# Micro.net
KiCad netlist of a schematic drawn in Altium Designer
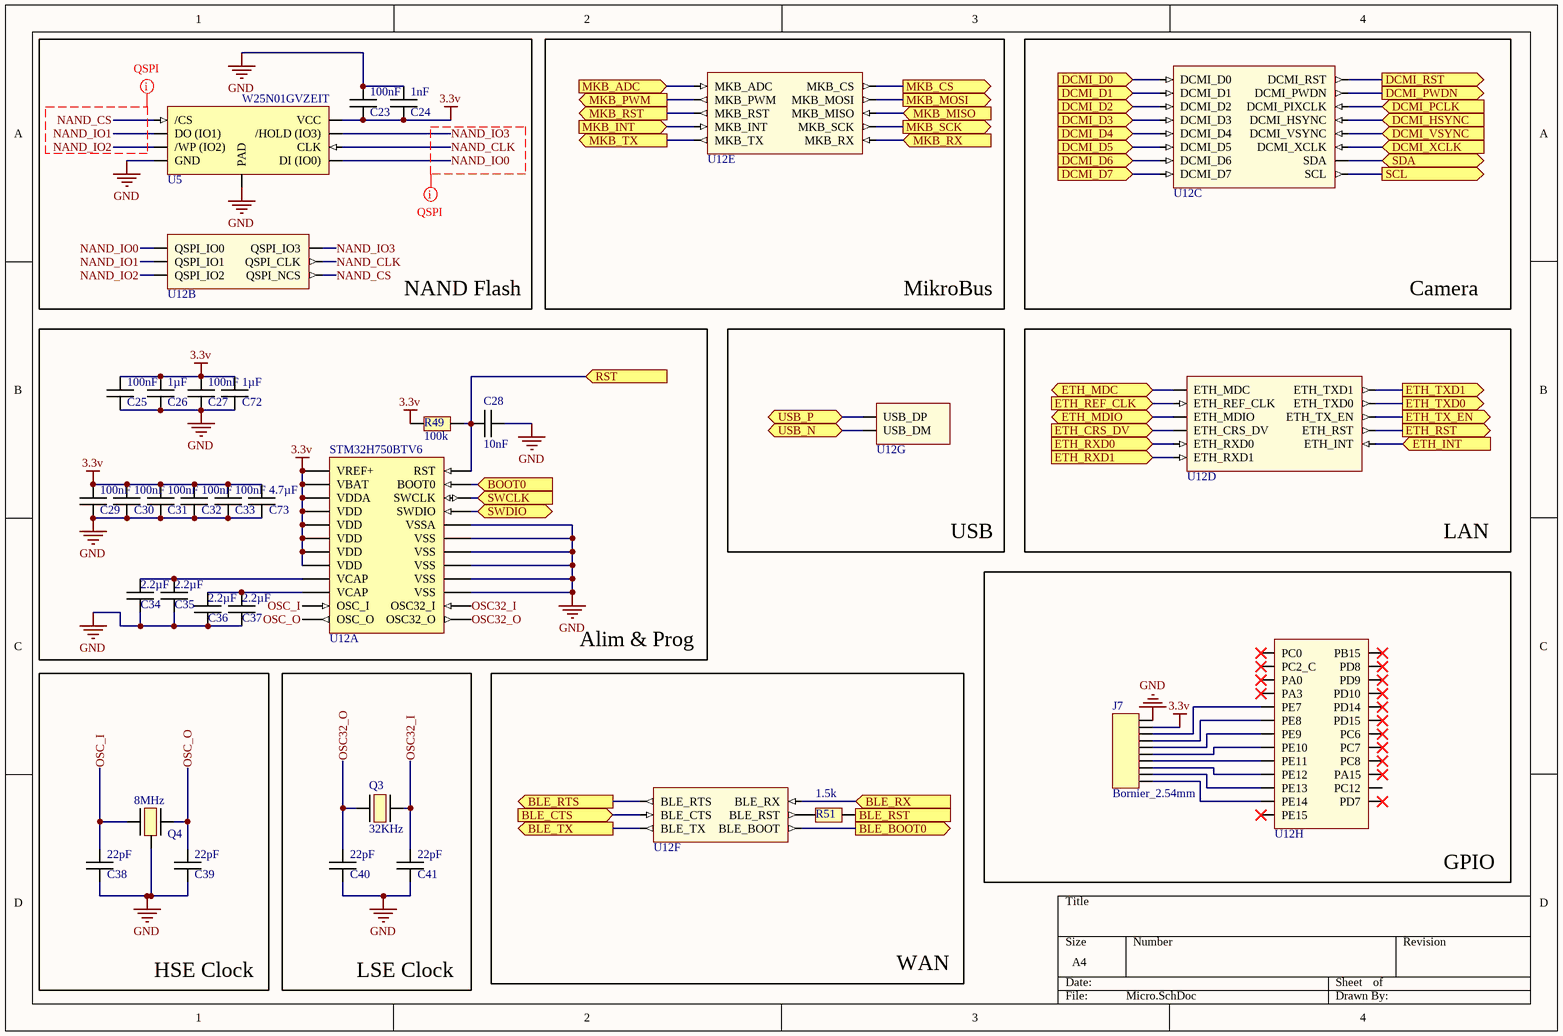
[diagram p0: Micro.SchDoc]

(export (version "E")
  (design (tool "Eeschema 10.0.6"))
  (components
    (comp (ref "C23")
      (value "100nF")
      (footprint "0603")
      (libsource (lib "Carte_design_SCHLib") (part "Capa"))
    )
    (comp (ref "C24") (value "1nF") (footprint "0603") (libsource (lib "Carte_design_SCHLib") (part "Capa")))
    (comp (ref "C25")
      (value "100nF")
      (footprint "0603")
      (libsource (lib "Carte_design_SCHLib") (part "Capa"))
    )
    (comp (ref "C26") (value "1µF") (footprint "0603") (libsource (lib "Carte_design_SCHLib") (part "Capa")))
    (comp (ref "C27")
      (value "100nF")
      (footprint "0603")
      (libsource (lib "Carte_design_SCHLib") (part "Capa"))
    )
    (comp (ref "C28") (value "10nF") (footprint "0603") (libsource (lib "Carte_design_SCHLib") (part "Capa")))
    (comp (ref "C29")
      (value "100nF")
      (footprint "0603")
      (libsource (lib "Carte_design_SCHLib") (part "Capa"))
    )
    (comp (ref "C30")
      (value "100nF")
      (footprint "0603")
      (libsource (lib "Carte_design_SCHLib") (part "Capa"))
    )
    (comp (ref "C31")
      (value "100nF")
      (footprint "0603")
      (libsource (lib "Carte_design_SCHLib") (part "Capa"))
    )
    (comp (ref "C32")
      (value "100nF")
      (footprint "0603")
      (libsource (lib "Carte_design_SCHLib") (part "Capa"))
    )
    (comp (ref "C33")
      (value "100nF")
      (footprint "0603")
      (libsource (lib "Carte_design_SCHLib") (part "Capa"))
    )
    (comp (ref "C34")
      (value "2.2µF")
      (footprint "0603")
      (libsource (lib "Carte_design_SCHLib") (part "Capa"))
    )
    (comp (ref "C35")
      (value "2.2µF")
      (footprint "0603")
      (libsource (lib "Carte_design_SCHLib") (part "Capa"))
    )
    (comp (ref "C36")
      (value "2.2µF")
      (footprint "0603")
      (libsource (lib "Carte_design_SCHLib") (part "Capa"))
    )
    (comp (ref "C37")
      (value "2.2µF")
      (footprint "0603")
      (libsource (lib "Carte_design_SCHLib") (part "Capa"))
    )
    (comp (ref "C38") (value "22pF") (footprint "0603") (libsource (lib "Carte_design_SCHLib") (part "Capa")))
    (comp (ref "C39") (value "22pF") (footprint "0603") (libsource (lib "Carte_design_SCHLib") (part "Capa")))
    (comp (ref "C40") (value "22pF") (footprint "0603") (libsource (lib "Carte_design_SCHLib") (part "Capa")))
    (comp (ref "C41") (value "22pF") (footprint "0603") (libsource (lib "Carte_design_SCHLib") (part "Capa")))
    (comp (ref "C72") (value "1µF") (footprint "0603") (libsource (lib "Carte_design_SCHLib") (part "Capa")))
    (comp (ref "C73")
      (value "4.7µF")
      (footprint "0603")
      (libsource (lib "Carte_design_SCHLib") (part "Capa"))
    )
    (comp (ref "J7")
      (value "Bornier_2.54mm")
      (footprint "GPIO_header")
      (libsource (lib "Carte_design_SCHLib") (part "GPIO_bornier"))
    )
    (comp (ref "Q3")
      (value "32KHz")
      (footprint "BLE_Quartz_Sxtal")
      (libsource (lib "Carte_design_SCHLib") (part "BLE_quartz_Sxtal"))
    )
    (comp (ref "Q4")
      (value "8MHz")
      (footprint "Quartz_Micro_HF")
      (libsource (lib "Carte_design_SCHLib") (part "Quartz_micro_HF"))
    )
    (comp (ref "R49")
      (value "100k")
      (footprint "0603")
      (libsource (lib "Carte_design_SCHLib") (part "Resistance"))
    )
    (comp (ref "R51")
      (value "1.5k")
      (footprint "0603")
      (libsource (lib "Carte_design_SCHLib") (part "Resistance"))
    )
    (comp (ref "U5")
      (value "W25N01GVZEIT")
      (footprint "SON127P800X80_HS-9M")
      (libsource (lib "Carte_design_SCHLib") (part "W25N01GVZEIT"))
    )
    (comp (ref "U12")
      (value "STM32H750BTV6")
      (footprint "LQFP100_14x14_0.5pitch")
      (libsource (lib "Carte_design_SCHLib") (part "STM32H750BTV6"))
    )
  )
  (nets
    (net (code "1") (name "/BLE_BOOT0") (class "Default")
      (node (ref "U12") (pin "81") (pinfunction "BLE_BOOT_81") (pintype "output"))
    )
    (net (code "2") (name "/BLE_CTS") (class "Default")
      (node (ref "U12") (pin "58") (pinfunction "BLE_CTS_58") (pintype "input"))
    )
    (net (code "3") (name "/BLE_RST") (class "Default")
      (node (ref "R51") (pin "1") (pinfunction "26_1") (pintype "passive"))
    )
    (net (code "4") (name "/BLE_RTS") (class "Default")
      (node (ref "U12") (pin "53") (pinfunction "BLE_RTS_53") (pintype "output"))
    )
    (net (code "5") (name "/BLE_RX") (class "Default")
      (node (ref "U12") (pin "79") (pinfunction "BLE_RX_79") (pintype "input"))
    )
    (net (code "6") (name "/BLE_TX") (class "Default")
      (node (ref "U12") (pin "78") (pinfunction "BLE_TX_78") (pintype "output"))
    )
    (net (code "7") (name "/BOOT0") (class "Default")
      (node (ref "U12") (pin "94") (pinfunction "BOOT0_94") (pintype "input"))
    )
    (net (code "8") (name "/DCMI_D0") (class "Default")
      (node (ref "U12") (pin "68") (pinfunction "DCMI_D0_68") (pintype "input"))
    )
    (net (code "9") (name "/DCMI_D1") (class "Default")
      (node (ref "U12") (pin "69") (pinfunction "DCMI_D1_69") (pintype "input"))
    )
    (net (code "10") (name "/DCMI_D2") (class "Default")
      (node (ref "U12") (pin "97") (pinfunction "DCMI_D2_97") (pintype "input"))
    )
    (net (code "11") (name "/DCMI_D3") (class "Default")
      (node (ref "U12") (pin "98") (pinfunction "DCMI_D3_98") (pintype "input"))
    )
    (net (code "12") (name "/DCMI_D4") (class "Default")
      (node (ref "U12") (pin "3") (pinfunction "DCMI_D4_3") (pintype "input"))
    )
    (net (code "13") (name "/DCMI_D5") (class "Default")
      (node (ref "U12") (pin "92") (pinfunction "DCMI_D5_92") (pintype "input"))
    )
    (net (code "14") (name "/DCMI_D6") (class "Default")
      (node (ref "U12") (pin "4") (pinfunction "DCMI_D6_4") (pintype "input"))
    )
    (net (code "15") (name "/DCMI_D7") (class "Default")
      (node (ref "U12") (pin "5") (pinfunction "DCMI_D7_5") (pintype "input"))
    )
    (net (code "16") (name "/DCMI_HSYNC") (class "Default")
      (node (ref "U12") (pin "28") (pinfunction "DCMI_HSYNC_28") (pintype "input"))
    )
    (net (code "17") (name "/DCMI_PCLK") (class "Default")
      (node (ref "U12") (pin "30") (pinfunction "DCMI_PIXCLK_30") (pintype "input"))
    )
    (net (code "18") (name "/DCMI_PWDN") (class "Default")
      (node (ref "U12") (pin "7") (pinfunction "DCMI_PWDN_7") (pintype "output"))
    )
    (net (code "19") (name "/DCMI_RST") (class "Default")
      (node (ref "U12") (pin "2") (pinfunction "DCMI_RST_2") (pintype "output"))
    )
    (net (code "20") (name "/DCMI_VSYNC") (class "Default")
      (node (ref "U12") (pin "93") (pinfunction "DCMI_VSYNC_93") (pintype "input"))
    )
    (net (code "21") (name "/DCMI_XCLK") (class "Default")
      (node (ref "U12") (pin "29") (pinfunction "DCMI_XCLK_29") (pintype "input"))
    )
    (net (code "22") (name "/ETH_CRS_DV") (class "Default")
      (node (ref "U12") (pin "31") (pinfunction "ETH_CRS_DV_31") (pintype "bidirectional"))
    )
    (net (code "23") (name "/ETH_INT") (class "Default")
      (node (ref "U12") (pin "34") (pinfunction "ETH_INT_34") (pintype "input"))
    )
    (net (code "24") (name "/ETH_MDC") (class "Default")
      (node (ref "U12") (pin "16") (pinfunction "ETH_MDC_16") (pintype "bidirectional"))
    )
    (net (code "25") (name "/ETH_MDIO") (class "Default")
      (node (ref "U12") (pin "24") (pinfunction "ETH_MDIO_24") (pintype "bidirectional"))
    )
    (net (code "26") (name "/ETH_REF_CLK") (class "Default")
      (node (ref "U12") (pin "23") (pinfunction "ETH_REF_CLK_23") (pintype "input"))
    )
    (net (code "27") (name "/ETH_RST") (class "Default")
      (node (ref "U12") (pin "35") (pinfunction "ETH_RST_35") (pintype "output"))
    )
    (net (code "28") (name "/ETH_RXD0") (class "Default")
      (node (ref "U12") (pin "32") (pinfunction "ETH_RXD0_32") (pintype "input"))
    )
    (net (code "29") (name "/ETH_RXD1") (class "Default")
      (node (ref "U12") (pin "33") (pinfunction "ETH_RXD1_33") (pintype "input"))
    )
    (net (code "30") (name "/ETH_TXD0") (class "Default")
      (node (ref "U12") (pin "51") (pinfunction "ETH_TXD0_51") (pintype "output"))
    )
    (net (code "31") (name "/ETH_TXD1") (class "Default")
      (node (ref "U12") (pin "52") (pinfunction "ETH_TXD1_52") (pintype "output"))
    )
    (net (code "32") (name "/ETH_TX_EN") (class "Default")
      (node (ref "U12") (pin "47") (pinfunction "ETH_TX_EN_47") (pintype "output"))
    )
    (net (code "33") (name "/MKB_ADC") (class "Default")
      (node (ref "U12") (pin "18") (pinfunction "MKB_ADC_18") (pintype "input"))
    )
    (net (code "34") (name "/MKB_CS") (class "Default")
      (node (ref "U12") (pin "85") (pinfunction "MKB_CS_85") (pintype "output"))
    )
    (net (code "35") (name "/MKB_INT") (class "Default")
      (node (ref "U12") (pin "84") (pinfunction "MKB_INT_84") (pintype "input"))
    )
    (net (code "36") (name "/MKB_MISO") (class "Default")
      (node (ref "U12") (pin "90") (pinfunction "MKB_MISO_90") (pintype "input"))
    )
    (net (code "37") (name "/MKB_MOSI") (class "Default")
      (node (ref "U12") (pin "91") (pinfunction "MKB_MOSI_91") (pintype "output"))
    )
    (net (code "38") (name "/MKB_PWM") (class "Default")
      (node (ref "U12") (pin "67") (pinfunction "MKB_PWM_67") (pintype "output"))
    )
    (net (code "39") (name "/MKB_RST") (class "Default")
      (node (ref "U12") (pin "83") (pinfunction "MKB_RST_83") (pintype "output"))
    )
    (net (code "40") (name "/MKB_RX") (class "Default")
      (node (ref "U12") (pin "87") (pinfunction "MKB_RX_87") (pintype "input"))
    )
    (net (code "41") (name "/MKB_SCK") (class "Default")
      (node (ref "U12") (pin "89") (pinfunction "MKB_SCK_89") (pintype "output"))
    )
    (net (code "42") (name "/MKB_TX") (class "Default")
      (node (ref "U12") (pin "86") (pinfunction "MKB_TX_86") (pintype "output"))
    )
    (net (code "43") (name "/NAND_CLK") (class "Default")
      (node (ref "U12") (pin "36") (pinfunction "QSPI_CLK_36") (pintype "output"))
      (node (ref "U5") (pin "6") (pinfunction "CLK_6") (pintype "input"))
    )
    (net (code "44") (name "/NAND_CS") (class "Default")
      (node (ref "U12") (pin "46") (pinfunction "QSPI_NCS_46") (pintype "output"))
      (node (ref "U5") (pin "1") (pinfunction "/CS_1") (pintype "input"))
    )
    (net (code "45") (name "/NAND_IO0") (class "Default")
      (node (ref "U12") (pin "66") (pinfunction "QSPI_IO0_66") (pintype "bidirectional"))
      (node (ref "U5") (pin "5") (pinfunction "DI_(IO0)_5") (pintype "bidirectional"))
    )
    (net (code "46") (name "/NAND_IO1") (class "Default")
      (node (ref "U12") (pin "59") (pinfunction "QSPI_IO1_59") (pintype "bidirectional"))
      (node (ref "U5") (pin "2") (pinfunction "DO_(IO1)_2") (pintype "bidirectional"))
    )
    (net (code "47") (name "/NAND_IO2") (class "Default")
      (node (ref "U12") (pin "1") (pinfunction "QSPI_IO2_1") (pintype "bidirectional"))
      (node (ref "U5") (pin "3") (pinfunction "/WP_(IO2)_3") (pintype "bidirectional"))
    )
    (net (code "48") (name "/NAND_IO3") (class "Default")
      (node (ref "U12") (pin "60") (pinfunction "QSPI_IO3_60") (pintype "bidirectional"))
      (node (ref "U5") (pin "7") (pinfunction "/HOLD_(IO3)_7") (pintype "bidirectional"))
    )
    (net (code "49") (name "/OSC32_I") (class "Default")
      (node (ref "C41") (pin "2") (pinfunction "28_2") (pintype "passive"))
      (node (ref "Q3") (pin "1") (pinfunction "15_1") (pintype "passive"))
      (node (ref "U12") (pin "8") (pinfunction "OSC32_I_8") (pintype "input"))
    )
    (net (code "50") (name "/OSC32_O") (class "Default")
      (node (ref "C40") (pin "2") (pinfunction "28_2") (pintype "passive"))
      (node (ref "Q3") (pin "2") (pinfunction "16_2") (pintype "passive"))
      (node (ref "U12") (pin "9") (pinfunction "OSC32_O_9") (pintype "output"))
    )
    (net (code "51") (name "/OSC_I") (class "Default")
      (node (ref "C38") (pin "2") (pinfunction "28_2") (pintype "passive"))
      (node (ref "Q4") (pin "1") (pinfunction "15_1") (pintype "passive"))
      (node (ref "U12") (pin "12") (pinfunction "OSC_I_12") (pintype "input"))
    )
    (net (code "52") (name "/OSC_O") (class "Default")
      (node (ref "C39") (pin "2") (pinfunction "28_2") (pintype "passive"))
      (node (ref "Q4") (pin "2") (pinfunction "16_2") (pintype "passive"))
      (node (ref "U12") (pin "13") (pinfunction "OSC_O_13") (pintype "output"))
    )
    (net (code "53") (name "/RST") (class "Default")
      (node (ref "C28") (pin "2") (pinfunction "28_2") (pintype "passive"))
      (node (ref "R49") (pin "1") (pinfunction "26_1") (pintype "passive"))
      (node (ref "U12") (pin "14") (pinfunction "RST_14") (pintype "input"))
    )
    (net (code "54") (name "/SCL") (class "Default")
      (node (ref "U12") (pin "95") (pinfunction "SCL_95") (pintype "output"))
    )
    (net (code "55") (name "/SDA") (class "Default")
      (node (ref "U12") (pin "96") (pinfunction "SDA_96") (pintype "bidirectional"))
    )
    (net (code "56") (name "/SWCLK") (class "Default")
      (node (ref "U12") (pin "76") (pinfunction "SWCLK_76") (pintype "bidirectional"))
    )
    (net (code "57") (name "/SWDIO") (class "Default")
      (node (ref "U12") (pin "72") (pinfunction "SWDIO_72") (pintype "input"))
    )
    (net (code "58") (name "/USB_N") (class "Default")
      (node (ref "U12") (pin "70") (pinfunction "USB_DM_70") (pintype "bidirectional"))
    )
    (net (code "59") (name "/USB_P") (class "Default")
      (node (ref "U12") (pin "71") (pinfunction "USB_DP_71") (pintype "bidirectional"))
    )
    (net (code "60") (name "3.3v") (class "Default")
      (node (ref "C23") (pin "1") (pinfunction "29_1") (pintype "passive"))
      (node (ref "C24") (pin "1") (pinfunction "29_1") (pintype "passive"))
      (node (ref "C25") (pin "2") (pinfunction "28_2") (pintype "passive"))
      (node (ref "C26") (pin "2") (pinfunction "28_2") (pintype "passive"))
      (node (ref "C27") (pin "2") (pinfunction "28_2") (pintype "passive"))
      (node (ref "C29") (pin "2") (pinfunction "28_2") (pintype "passive"))
      (node (ref "C30") (pin "2") (pinfunction "28_2") (pintype "passive"))
      (node (ref "C31") (pin "2") (pinfunction "28_2") (pintype "passive"))
      (node (ref "C32") (pin "2") (pinfunction "28_2") (pintype "passive"))
      (node (ref "C33") (pin "2") (pinfunction "28_2") (pintype "passive"))
      (node (ref "C72") (pin "2") (pinfunction "28_2") (pintype "passive"))
      (node (ref "C73") (pin "2") (pinfunction "28_2") (pintype "passive"))
      (node (ref "J7") (pin "9") (pintype "passive"))
      (node (ref "R49") (pin "2") (pinfunction "27_2") (pintype "passive"))
      (node (ref "U12") (pin "100") (pinfunction "VDD_100") (pintype "power_in"))
      (node (ref "U12") (pin "11") (pinfunction "VDD_11") (pintype "power_in"))
      (node (ref "U12") (pin "20") (pinfunction "VREF+_20") (pintype "power_in"))
      (node (ref "U12") (pin "21") (pinfunction "VDDA_21") (pintype "power_in"))
      (node (ref "U12") (pin "27") (pinfunction "VDD_27") (pintype "power_in"))
      (node (ref "U12") (pin "50") (pinfunction "VDD_50") (pintype "power_in"))
      (node (ref "U12") (pin "6") (pinfunction "VBAT_6") (pintype "power_in"))
      (node (ref "U12") (pin "75") (pinfunction "VDD_75") (pintype "power_in"))
      (node (ref "U5") (pin "8") (pinfunction "VCC_8") (pintype "power_in"))
    )
    (net (code "61") (name "GND") (class "Default")
      (node (ref "C23") (pin "2") (pinfunction "28_2") (pintype "passive"))
      (node (ref "C24") (pin "2") (pinfunction "28_2") (pintype "passive"))
      (node (ref "C25") (pin "1") (pinfunction "29_1") (pintype "passive"))
      (node (ref "C26") (pin "1") (pinfunction "29_1") (pintype "passive"))
      (node (ref "C27") (pin "1") (pinfunction "29_1") (pintype "passive"))
      (node (ref "C28") (pin "1") (pinfunction "29_1") (pintype "passive"))
      (node (ref "C29") (pin "1") (pinfunction "29_1") (pintype "passive"))
      (node (ref "C30") (pin "1") (pinfunction "29_1") (pintype "passive"))
      (node (ref "C31") (pin "1") (pinfunction "29_1") (pintype "passive"))
      (node (ref "C32") (pin "1") (pinfunction "29_1") (pintype "passive"))
      (node (ref "C33") (pin "1") (pinfunction "29_1") (pintype "passive"))
      (node (ref "C34") (pin "1") (pinfunction "29_1") (pintype "passive"))
      (node (ref "C35") (pin "1") (pinfunction "29_1") (pintype "passive"))
      (node (ref "C36") (pin "1") (pinfunction "29_1") (pintype "passive"))
      (node (ref "C37") (pin "1") (pinfunction "29_1") (pintype "passive"))
      (node (ref "C38") (pin "1") (pinfunction "29_1") (pintype "passive"))
      (node (ref "C39") (pin "1") (pinfunction "29_1") (pintype "passive"))
      (node (ref "C40") (pin "1") (pinfunction "29_1") (pintype "passive"))
      (node (ref "C41") (pin "1") (pinfunction "29_1") (pintype "passive"))
      (node (ref "C72") (pin "1") (pinfunction "29_1") (pintype "passive"))
      (node (ref "C73") (pin "1") (pinfunction "29_1") (pintype "passive"))
      (node (ref "J7") (pin "10") (pintype "passive"))
      (node (ref "Q4") (pin "3") (pinfunction "3_3") (pintype "passive"))
      (node (ref "U12") (pin "10") (pinfunction "VSS_10") (pintype "power_in"))
      (node (ref "U12") (pin "19") (pinfunction "VSSA_19") (pintype "power_in"))
      (node (ref "U12") (pin "26") (pinfunction "VSS_26") (pintype "power_in"))
      (node (ref "U12") (pin "49") (pinfunction "VSS_49") (pintype "power_in"))
      (node (ref "U12") (pin "74") (pinfunction "VSS_74") (pintype "power_in"))
      (node (ref "U12") (pin "99") (pinfunction "VSS_99") (pintype "power_in"))
      (node (ref "U5") (pin "4") (pinfunction "GND_4") (pintype "power_in"))
      (node (ref "U5") (pin "9") (pinfunction "PAD_9") (pintype "power_in"))
    )
    (net (code "62") (name "Net-(C34-28)") (class "Default")
      (node (ref "C34") (pin "2") (pinfunction "28_2") (pintype "passive"))
      (node (ref "C35") (pin "2") (pinfunction "28_2") (pintype "passive"))
      (node (ref "U12") (pin "48") (pinfunction "VCAP_48") (pintype "power_in"))
    )
    (net (code "63") (name "Net-(C36-28)") (class "Default")
      (node (ref "C36") (pin "2") (pinfunction "28_2") (pintype "passive"))
      (node (ref "C37") (pin "2") (pinfunction "28_2") (pintype "passive"))
      (node (ref "U12") (pin "73") (pinfunction "VCAP_73") (pintype "power_in"))
    )
    (net (code "64") (name "Net-(R51-27)") (class "Default")
      (node (ref "R51") (pin "2") (pinfunction "27_2") (pintype "passive"))
      (node (ref "U12") (pin "82") (pinfunction "BLE_RST_82") (pintype "output"))
    )
    (net (code "65") (name "Net-(U12H-PE7)") (class "Default")
      (node (ref "J7") (pin "8") (pintype "passive"))
      (node (ref "U12") (pin "37") (pinfunction "PE7_37") (pintype "bidirectional"))
    )
    (net (code "66") (name "Net-(U12H-PE8)") (class "Default")
      (node (ref "J7") (pin "7") (pintype "passive"))
      (node (ref "U12") (pin "38") (pinfunction "PE8_38") (pintype "bidirectional"))
    )
    (net (code "67") (name "Net-(U12H-PE9)") (class "Default")
      (node (ref "J7") (pin "6") (pintype "passive"))
      (node (ref "U12") (pin "39") (pinfunction "PE9_39") (pintype "bidirectional"))
    )
    (net (code "68") (name "Net-(U12H-PE10)") (class "Default")
      (node (ref "J7") (pin "5") (pintype "passive"))
      (node (ref "U12") (pin "40") (pinfunction "PE10_40") (pintype "bidirectional"))
    )
    (net (code "69") (name "Net-(U12H-PE11)") (class "Default")
      (node (ref "J7") (pin "4") (pintype "passive"))
      (node (ref "U12") (pin "41") (pinfunction "PE11_41") (pintype "bidirectional"))
    )
    (net (code "70") (name "Net-(U12H-PE12)") (class "Default")
      (node (ref "J7") (pin "3") (pintype "passive"))
      (node (ref "U12") (pin "42") (pinfunction "PE12_42") (pintype "bidirectional"))
    )
    (net (code "71") (name "Net-(U12H-PE13)") (class "Default")
      (node (ref "J7") (pin "2") (pintype "passive"))
      (node (ref "U12") (pin "43") (pinfunction "PE13_43") (pintype "bidirectional"))
    )
    (net (code "72") (name "Net-(U12H-PE14)") (class "Default")
      (node (ref "J7") (pin "1") (pintype "passive"))
      (node (ref "U12") (pin "44") (pinfunction "PE14_44") (pintype "bidirectional"))
    )
    (net (code "73") (name "unconnected-(U12H-PA0-Pad22)") (class "Default")
      (node (ref "U12") (pin "22") (pinfunction "PA0_22") (pintype "bidirectional+no_connect"))
    )
    (net (code "74") (name "unconnected-(U12H-PA3-Pad25)") (class "Default")
      (node (ref "U12") (pin "25") (pinfunction "PA3_25") (pintype "bidirectional+no_connect"))
    )
    (net (code "75") (name "unconnected-(U12H-PA15-Pad77)") (class "Default")
      (node (ref "U12") (pin "77") (pinfunction "PA15_77") (pintype "bidirectional+no_connect"))
    )
    (net (code "76") (name "unconnected-(U12H-PB15-Pad54)") (class "Default")
      (node (ref "U12") (pin "54") (pinfunction "PB15_54") (pintype "bidirectional+no_connect"))
    )
    (net (code "77") (name "unconnected-(U12H-PC0-Pad15)") (class "Default")
      (node (ref "U12") (pin "15") (pinfunction "PC0_15") (pintype "bidirectional+no_connect"))
    )
    (net (code "78") (name "unconnected-(U12H-PC2_C-Pad17)") (class "Default")
      (node (ref "U12") (pin "17") (pinfunction "PC2_C_17") (pintype "bidirectional+no_connect"))
    )
    (net (code "79") (name "unconnected-(U12H-PC6-Pad63)") (class "Default")
      (node (ref "U12") (pin "63") (pinfunction "PC6_63") (pintype "bidirectional+no_connect"))
    )
    (net (code "80") (name "unconnected-(U12H-PC7-Pad64)") (class "Default")
      (node (ref "U12") (pin "64") (pinfunction "PC7_64") (pintype "bidirectional+no_connect"))
    )
    (net (code "81") (name "unconnected-(U12H-PC8-Pad65)") (class "Default")
      (node (ref "U12") (pin "65") (pinfunction "PC8_65") (pintype "bidirectional+no_connect"))
    )
    (net (code "82") (name "unconnected-(U12H-PC12-Pad80)") (class "Default")
      (node (ref "U12") (pin "80") (pinfunction "PC12_80") (pintype "bidirectional"))
    )
    (net (code "83") (name "unconnected-(U12H-PD7-Pad88)") (class "Default")
      (node (ref "U12") (pin "88") (pinfunction "PD7_88") (pintype "bidirectional+no_connect"))
    )
    (net (code "84") (name "unconnected-(U12H-PD8-Pad55)") (class "Default")
      (node (ref "U12") (pin "55") (pinfunction "PD8_55") (pintype "bidirectional+no_connect"))
    )
    (net (code "85") (name "unconnected-(U12H-PD9-Pad56)") (class "Default")
      (node (ref "U12") (pin "56") (pinfunction "PD9_56") (pintype "bidirectional+no_connect"))
    )
    (net (code "86") (name "unconnected-(U12H-PD10-Pad57)") (class "Default")
      (node (ref "U12") (pin "57") (pinfunction "PD10_57") (pintype "bidirectional+no_connect"))
    )
    (net (code "87") (name "unconnected-(U12H-PD14-Pad61)") (class "Default")
      (node (ref "U12") (pin "61") (pinfunction "PD14_61") (pintype "bidirectional+no_connect"))
    )
    (net (code "88") (name "unconnected-(U12H-PD15-Pad62)") (class "Default")
      (node (ref "U12") (pin "62") (pinfunction "PD15_62") (pintype "bidirectional+no_connect"))
    )
    (net (code "89") (name "unconnected-(U12H-PE15-Pad45)") (class "Default")
      (node (ref "U12") (pin "45") (pinfunction "PE15_45") (pintype "bidirectional+no_connect"))
    )
  )
)
